# Oscar_MainBoard_WIFI.net
KiCad netlist of a schematic drawn in Altium Designer
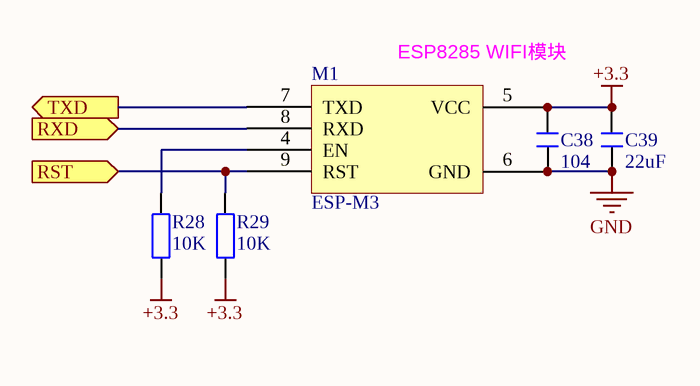
[diagram p0: Oscar_MainBoard_WIFI.SchDoc]

(export (version "E")
  (design (tool "Eeschema 10.0.6"))
  (components
    (comp (ref "C38")
      (value "104")
      (footprint "C 0402_L")
      (description "贴片电容")
      (libsource (lib "0.1 - 电阻-电容-电感") (part "C"))
    )
    (comp (ref "C39")
      (value "22uF")
      (footprint "C 0805_L")
      (description "贴片电容")
      (libsource (lib "0.1 - 电阻-电容-电感") (part "C"))
    )
    (comp (ref "M1")
      (value "ESP-M3")
      (footprint "ESP-M3")
      (description "四博智联ESP-M3无线模块")
      (libsource (lib "无线模块") (part "ESP-M3"))
    )
    (comp (ref "R28")
      (value "10K")
      (footprint "R 0402_L")
      (description "贴片电阻")
      (libsource (lib "0.1 - 电阻-电容-电感") (part "R"))
    )
    (comp (ref "R29")
      (value "10K")
      (footprint "R 0402_L")
      (description "贴片电阻")
      (libsource (lib "0.1 - 电阻-电容-电感") (part "R"))
    )
  )
  (nets
    (net (code "1") (name "+3.3") (class "Default")
      (node (ref "C38") (pin "2") (pinfunction "2_2") (pintype "passive"))
      (node (ref "C39") (pin "2") (pinfunction "2_2") (pintype "passive"))
      (node (ref "M1") (pin "5") (pinfunction "VCC_5") (pintype "passive"))
      (node (ref "R28") (pin "1") (pinfunction "1_1") (pintype "passive"))
      (node (ref "R29") (pin "1") (pinfunction "1_1") (pintype "passive"))
    )
    (net (code "2") (name "/RST") (class "Default")
      (node (ref "M1") (pin "9") (pinfunction "RST_9") (pintype "passive"))
      (node (ref "R29") (pin "2") (pinfunction "2_2") (pintype "passive"))
    )
    (net (code "3") (name "/RXD") (class "Default")
      (node (ref "M1") (pin "8") (pinfunction "RXD_8") (pintype "passive"))
    )
    (net (code "4") (name "/TXD") (class "Default")
      (node (ref "M1") (pin "7") (pinfunction "TXD_7") (pintype "passive"))
    )
    (net (code "5") (name "GND") (class "Default")
      (node (ref "C38") (pin "1") (pinfunction "1_1") (pintype "passive"))
      (node (ref "C39") (pin "1") (pinfunction "1_1") (pintype "passive"))
      (node (ref "M1") (pin "6") (pinfunction "GND_6") (pintype "passive"))
    )
    (net (code "6") (name "Net-(M1-EN)") (class "Default")
      (node (ref "M1") (pin "4") (pinfunction "EN_4") (pintype "passive"))
      (node (ref "R28") (pin "2") (pinfunction "2_2") (pintype "passive"))
    )
  )
)
